# M602A.net
KiCad netlist of a schematic drawn in EAGLE
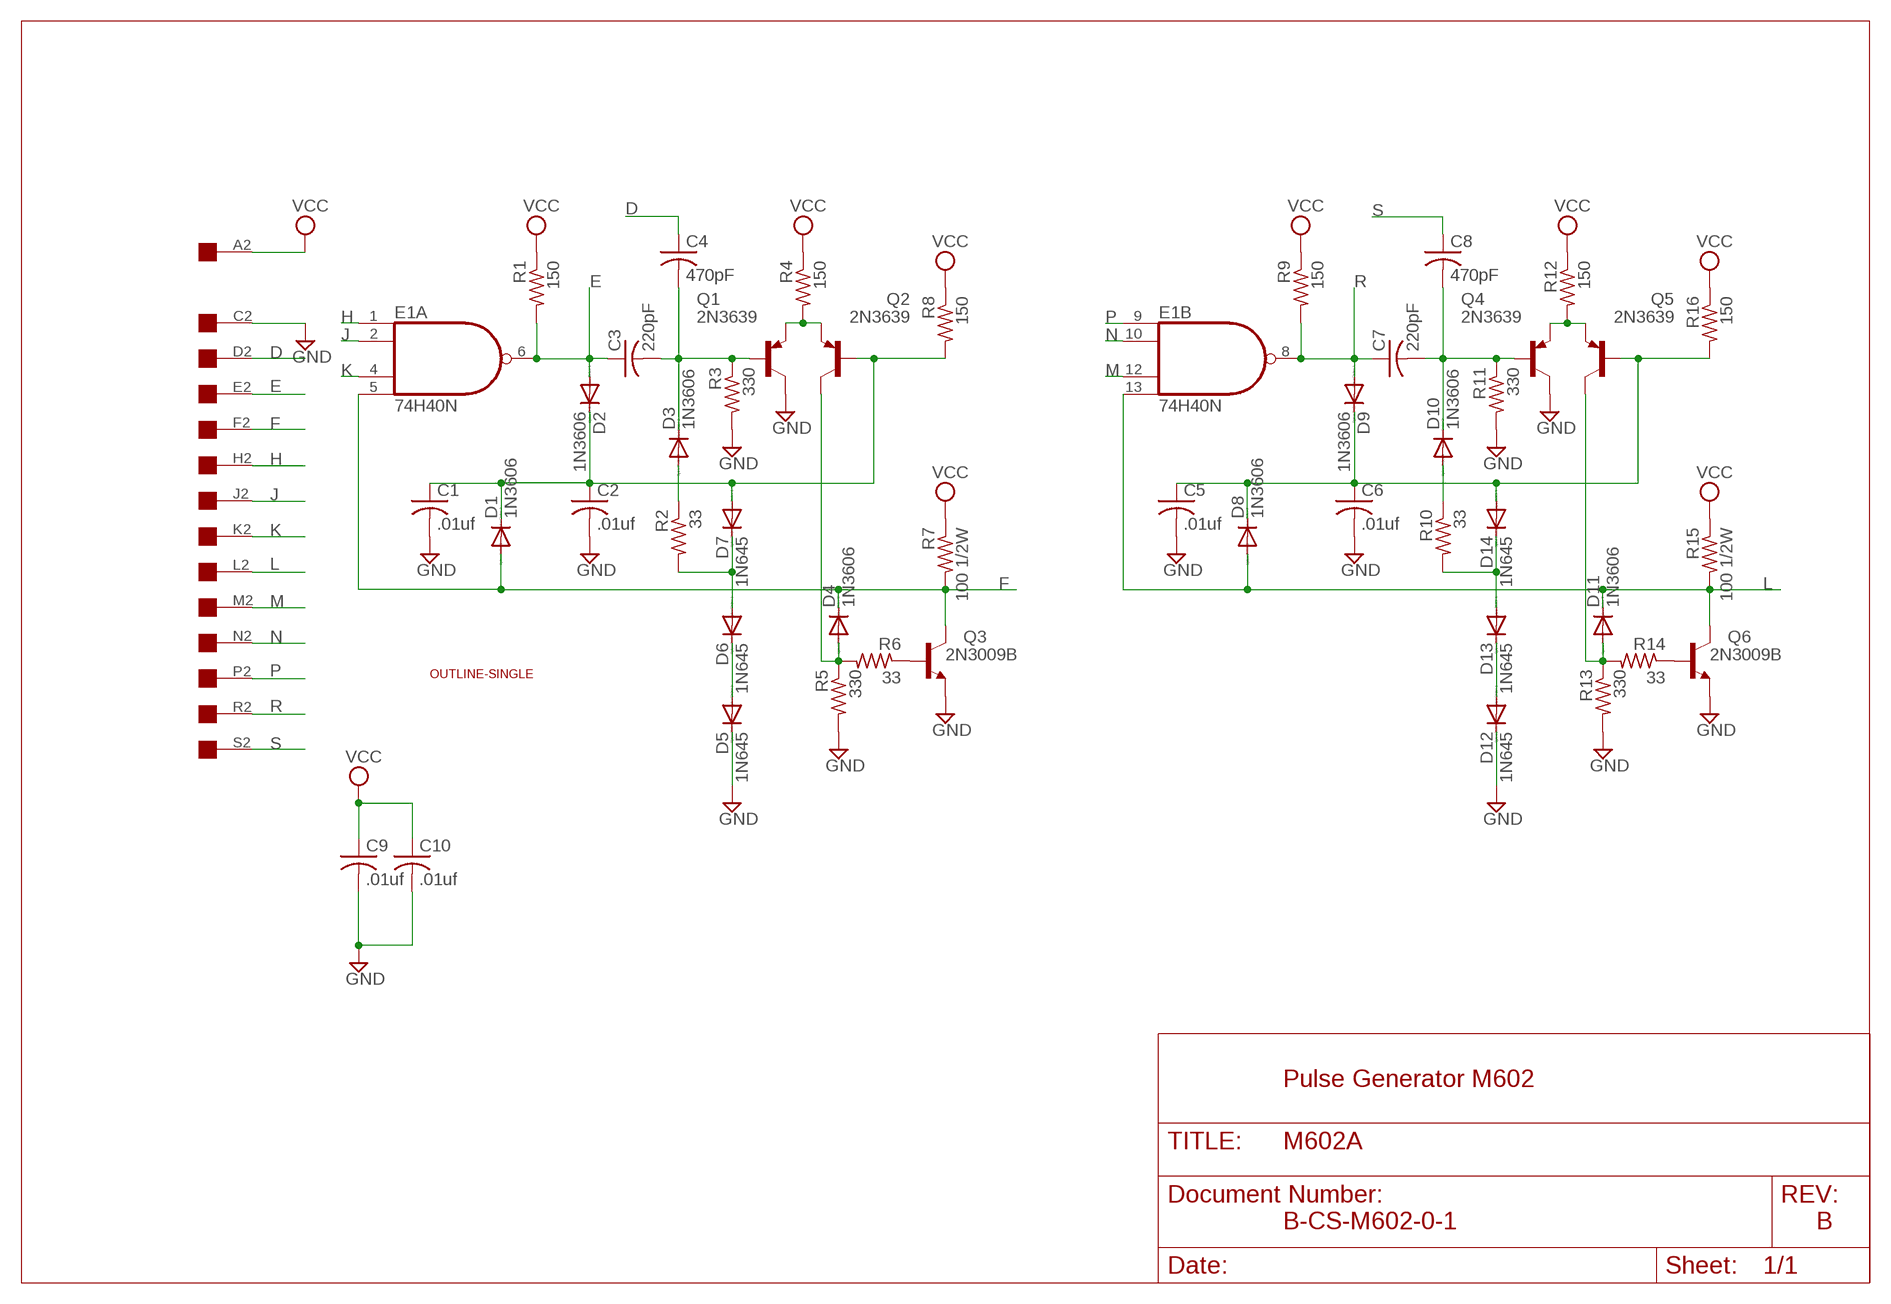
[diagram p0: schematic, sheet 1]

(export (version "E")
  (design (tool "Eeschema 10.0.6"))
  (components
    (comp (ref "C1")
      (value ".01uf")
      (footprint "eagle-import:C075-032X103")
      (libsource (lib "eagle-import") (part "C-US075-032X103"))
    )
    (comp (ref "C2")
      (value ".01uf")
      (footprint "eagle-import:C075-032X103")
      (libsource (lib "eagle-import") (part "C-US075-032X103"))
    )
    (comp (ref "C3")
      (value "220pF")
      (footprint "eagle-import:C150-054X183")
      (libsource (lib "eagle-import") (part "C-US150-054X183"))
    )
    (comp (ref "C4")
      (value "470pF")
      (footprint "eagle-import:C150-054X183")
      (libsource (lib "eagle-import") (part "C-US150-054X183"))
    )
    (comp (ref "C5")
      (value ".01uf")
      (footprint "eagle-import:C075-032X103")
      (libsource (lib "eagle-import") (part "C-US075-032X103"))
    )
    (comp (ref "C6")
      (value ".01uf")
      (footprint "eagle-import:C075-032X103")
      (libsource (lib "eagle-import") (part "C-US075-032X103"))
    )
    (comp (ref "C7")
      (value "220pF")
      (footprint "eagle-import:C150-054X183")
      (libsource (lib "eagle-import") (part "C-US150-054X183"))
    )
    (comp (ref "C8")
      (value "470pF")
      (footprint "eagle-import:C150-054X183")
      (libsource (lib "eagle-import") (part "C-US150-054X183"))
    )
    (comp (ref "C9")
      (value ".01uf")
      (footprint "eagle-import:C050-025X075")
      (libsource (lib "eagle-import") (part "C-US050-025X075"))
    )
    (comp (ref "C10")
      (value ".01uf")
      (footprint "eagle-import:C075-032X103")
      (libsource (lib "eagle-import") (part "C-US075-032X103"))
    )
    (comp (ref "D1")
      (value "1N3606")
      (footprint "eagle-import:DO41-10")
      (libsource (lib "eagle-import") (part "1N4004"))
    )
    (comp (ref "D2")
      (value "1N3606")
      (footprint "eagle-import:DO41-10")
      (libsource (lib "eagle-import") (part "1N4004"))
    )
    (comp (ref "D3")
      (value "1N3606")
      (footprint "eagle-import:DO41-10")
      (libsource (lib "eagle-import") (part "1N4004"))
    )
    (comp (ref "D4")
      (value "1N3606")
      (footprint "eagle-import:DO41-10")
      (libsource (lib "eagle-import") (part "1N4004"))
    )
    (comp (ref "D5")
      (value "1N645")
      (footprint "eagle-import:DO41-10")
      (libsource (lib "eagle-import") (part "1N4004"))
    )
    (comp (ref "D6")
      (value "1N645")
      (footprint "eagle-import:DO41-10")
      (libsource (lib "eagle-import") (part "1N4004"))
    )
    (comp (ref "D7")
      (value "1N645")
      (footprint "eagle-import:DO41-10")
      (libsource (lib "eagle-import") (part "1N4004"))
    )
    (comp (ref "D8")
      (value "1N3606")
      (footprint "eagle-import:DO41-10")
      (libsource (lib "eagle-import") (part "1N4004"))
    )
    (comp (ref "D9")
      (value "1N3606")
      (footprint "eagle-import:DO41-10")
      (libsource (lib "eagle-import") (part "1N4004"))
    )
    (comp (ref "D10")
      (value "1N3606")
      (footprint "eagle-import:DO41-10")
      (libsource (lib "eagle-import") (part "1N4004"))
    )
    (comp (ref "D11")
      (value "1N3606")
      (footprint "eagle-import:DO41-10")
      (libsource (lib "eagle-import") (part "1N4004"))
    )
    (comp (ref "D12")
      (value "1N645")
      (footprint "eagle-import:DO41-10")
      (libsource (lib "eagle-import") (part "1N4004"))
    )
    (comp (ref "D13")
      (value "1N645")
      (footprint "eagle-import:DO41-10")
      (libsource (lib "eagle-import") (part "1N4004"))
    )
    (comp (ref "D14")
      (value "1N645")
      (footprint "eagle-import:DO41-10")
      (libsource (lib "eagle-import") (part "1N4004"))
    )
    (comp (ref "E1")
      (value "74H40N")
      (footprint "eagle-import:DIL14")
      (libsource (lib "eagle-import") (part "7420NLS"))
    )
    (comp (ref "Q1")
      (value "2N3639")
      (footprint "eagle-import:TO39")
      (libsource (lib "eagle-import") (part "2N5415"))
    )
    (comp (ref "Q2")
      (value "2N3639")
      (footprint "eagle-import:TO39")
      (libsource (lib "eagle-import") (part "2N5415"))
    )
    (comp (ref "Q3")
      (value "2N3009B")
      (footprint "eagle-import:TO39")
      (libsource (lib "eagle-import") (part "2N1711"))
    )
    (comp (ref "Q4")
      (value "2N3639")
      (footprint "eagle-import:TO39")
      (libsource (lib "eagle-import") (part "2N5415"))
    )
    (comp (ref "Q5")
      (value "2N3639")
      (footprint "eagle-import:TO39")
      (libsource (lib "eagle-import") (part "2N5415"))
    )
    (comp (ref "Q6")
      (value "2N3009B")
      (footprint "eagle-import:TO39")
      (libsource (lib "eagle-import") (part "2N1711"))
    )
    (comp (ref "R1")
      (value "150")
      (footprint "eagle-import:0207_10")
      (libsource (lib "eagle-import") (part "R-US_0207/10"))
    )
    (comp (ref "R2")
      (value "33")
      (footprint "eagle-import:0207_10")
      (libsource (lib "eagle-import") (part "R-US_0207/10"))
    )
    (comp (ref "R3")
      (value "330")
      (footprint "eagle-import:0207_10")
      (libsource (lib "eagle-import") (part "R-US_0207/10"))
    )
    (comp (ref "R4")
      (value "150")
      (footprint "eagle-import:0207_10")
      (libsource (lib "eagle-import") (part "R-US_0207/10"))
    )
    (comp (ref "R5")
      (value "330")
      (footprint "eagle-import:0207_10")
      (libsource (lib "eagle-import") (part "R-US_0207/10"))
    )
    (comp (ref "R6")
      (value "33")
      (footprint "eagle-import:0207_10")
      (libsource (lib "eagle-import") (part "R-US_0207/10"))
    )
    (comp (ref "R7")
      (value "100 1/2W")
      (footprint "eagle-import:0309_12")
      (libsource (lib "eagle-import") (part "R-US_0309/12"))
    )
    (comp (ref "R8")
      (value "150")
      (footprint "eagle-import:0207_10")
      (libsource (lib "eagle-import") (part "R-US_0207/10"))
    )
    (comp (ref "R9")
      (value "150")
      (footprint "eagle-import:0207_10")
      (libsource (lib "eagle-import") (part "R-US_0207/10"))
    )
    (comp (ref "R10")
      (value "33")
      (footprint "eagle-import:0207_10")
      (libsource (lib "eagle-import") (part "R-US_0207/10"))
    )
    (comp (ref "R11")
      (value "330")
      (footprint "eagle-import:0207_10")
      (libsource (lib "eagle-import") (part "R-US_0207/10"))
    )
    (comp (ref "R12")
      (value "150")
      (footprint "eagle-import:0207_10")
      (libsource (lib "eagle-import") (part "R-US_0207/10"))
    )
    (comp (ref "R13")
      (value "330")
      (footprint "eagle-import:0207_10")
      (libsource (lib "eagle-import") (part "R-US_0207/10"))
    )
    (comp (ref "R14")
      (value "33")
      (footprint "eagle-import:0207_10")
      (libsource (lib "eagle-import") (part "R-US_0207/10"))
    )
    (comp (ref "R15")
      (value "100 1/2W")
      (footprint "eagle-import:0309_12")
      (libsource (lib "eagle-import") (part "R-US_0309/12"))
    )
    (comp (ref "R16")
      (value "150")
      (footprint "eagle-import:0207_10")
      (libsource (lib "eagle-import") (part "R-US_0207/10"))
    )
    (comp (ref "U$1")
      (value "EDGE-1")
      (footprint "eagle-import:EDGE-CON1")
      (libsource (lib "eagle-import") (part "EDGE-1"))
    )
    (comp (ref "U$2")
      (value "OUTLINE-SINGLE")
      (footprint "eagle-import:SINGLE")
      (libsource (lib "eagle-import") (part "OUTLINE-SINGLE"))
    )
  )
  (nets
    (net (code "1") (name "/D") (class "Default")
      (node (ref "C4") (pin "1") (pinfunction "1_1") (pintype "passive"))
      (node (ref "U$1") (pin "D2") (pinfunction "1_D2") (pintype "bidirectional"))
    )
    (net (code "2") (name "/E") (class "Default")
      (node (ref "C3") (pin "1") (pinfunction "1_1") (pintype "passive"))
      (node (ref "D2") (pin "A") (pinfunction "A_A") (pintype "passive"))
      (node (ref "E1") (pin "6") (pinfunction "O_6") (pintype "output"))
      (node (ref "R1") (pin "2") (pinfunction "2_2") (pintype "passive"))
      (node (ref "U$1") (pin "E2") (pinfunction "1_E2") (pintype "bidirectional"))
    )
    (net (code "3") (name "/F") (class "Default")
      (node (ref "D1") (pin "A") (pinfunction "A_A") (pintype "passive"))
      (node (ref "D4") (pin "C") (pinfunction "C_C") (pintype "passive"))
      (node (ref "E1") (pin "5") (pinfunction "I3_5") (pintype "input"))
      (node (ref "Q3") (pin "3") (pinfunction "C_3") (pintype "passive"))
      (node (ref "R7") (pin "2") (pinfunction "2_2") (pintype "passive"))
      (node (ref "U$1") (pin "F2") (pinfunction "1_F2") (pintype "bidirectional"))
    )
    (net (code "4") (name "/H") (class "Default")
      (node (ref "E1") (pin "1") (pinfunction "I0_1") (pintype "input"))
      (node (ref "U$1") (pin "H2") (pinfunction "1_H2") (pintype "bidirectional"))
    )
    (net (code "5") (name "/J") (class "Default")
      (node (ref "E1") (pin "2") (pinfunction "I1_2") (pintype "input"))
      (node (ref "U$1") (pin "J2") (pinfunction "1_J2") (pintype "bidirectional"))
    )
    (net (code "6") (name "/K") (class "Default")
      (node (ref "E1") (pin "4") (pinfunction "I2_4") (pintype "input"))
      (node (ref "U$1") (pin "K2") (pinfunction "1_K2") (pintype "bidirectional"))
    )
    (net (code "7") (name "/L") (class "Default")
      (node (ref "D11") (pin "C") (pinfunction "C_C") (pintype "passive"))
      (node (ref "D8") (pin "A") (pinfunction "A_A") (pintype "passive"))
      (node (ref "E1") (pin "13") (pinfunction "I3_13") (pintype "input"))
      (node (ref "Q6") (pin "3") (pinfunction "C_3") (pintype "passive"))
      (node (ref "R15") (pin "2") (pinfunction "2_2") (pintype "passive"))
      (node (ref "U$1") (pin "L2") (pinfunction "1_L2") (pintype "bidirectional"))
    )
    (net (code "8") (name "/M") (class "Default")
      (node (ref "E1") (pin "12") (pinfunction "I2_12") (pintype "input"))
      (node (ref "U$1") (pin "M2") (pinfunction "1_M2") (pintype "bidirectional"))
    )
    (net (code "9") (name "/N") (class "Default")
      (node (ref "E1") (pin "10") (pinfunction "I1_10") (pintype "input"))
      (node (ref "U$1") (pin "N2") (pinfunction "1_N2") (pintype "bidirectional"))
    )
    (net (code "10") (name "/P") (class "Default")
      (node (ref "E1") (pin "9") (pinfunction "I0_9") (pintype "input"))
      (node (ref "U$1") (pin "P2") (pinfunction "1_P2") (pintype "bidirectional"))
    )
    (net (code "11") (name "/R") (class "Default")
      (node (ref "C7") (pin "1") (pinfunction "1_1") (pintype "passive"))
      (node (ref "D9") (pin "A") (pinfunction "A_A") (pintype "passive"))
      (node (ref "E1") (pin "8") (pinfunction "O_8") (pintype "output"))
      (node (ref "R9") (pin "2") (pinfunction "2_2") (pintype "passive"))
      (node (ref "U$1") (pin "R2") (pinfunction "1_R2") (pintype "bidirectional"))
    )
    (net (code "12") (name "/S") (class "Default")
      (node (ref "C8") (pin "1") (pinfunction "1_1") (pintype "passive"))
      (node (ref "U$1") (pin "S2") (pinfunction "1_S2") (pintype "bidirectional"))
    )
    (net (code "13") (name "GND") (class "Default")
      (node (ref "C1") (pin "2") (pinfunction "2_2") (pintype "passive"))
      (node (ref "C10") (pin "2") (pinfunction "2_2") (pintype "passive"))
      (node (ref "C2") (pin "2") (pinfunction "2_2") (pintype "passive"))
      (node (ref "C5") (pin "2") (pinfunction "2_2") (pintype "passive"))
      (node (ref "C6") (pin "2") (pinfunction "2_2") (pintype "passive"))
      (node (ref "C9") (pin "2") (pinfunction "2_2") (pintype "passive"))
      (node (ref "D12") (pin "C") (pinfunction "C_C") (pintype "passive"))
      (node (ref "D5") (pin "C") (pinfunction "C_C") (pintype "passive"))
      (node (ref "Q1") (pin "3") (pinfunction "C_3") (pintype "passive"))
      (node (ref "Q3") (pin "1") (pinfunction "E_1") (pintype "passive"))
      (node (ref "Q4") (pin "3") (pinfunction "C_3") (pintype "passive"))
      (node (ref "Q6") (pin "1") (pinfunction "E_1") (pintype "passive"))
      (node (ref "R11") (pin "2") (pinfunction "2_2") (pintype "passive"))
      (node (ref "R13") (pin "2") (pinfunction "2_2") (pintype "passive"))
      (node (ref "R3") (pin "2") (pinfunction "2_2") (pintype "passive"))
      (node (ref "R5") (pin "2") (pinfunction "2_2") (pintype "passive"))
      (node (ref "U$1") (pin "C2") (pinfunction "1_C2") (pintype "bidirectional"))
    )
    (net (code "14") (name "Net-(D3-PadA)") (class "Default")
      (node (ref "D3") (pin "A") (pinfunction "A_A") (pintype "passive"))
      (node (ref "R2") (pin "1") (pinfunction "1_1") (pintype "passive"))
    )
    (net (code "15") (name "Net-(D5-PadA)") (class "Default")
      (node (ref "D5") (pin "A") (pinfunction "A_A") (pintype "passive"))
      (node (ref "D6") (pin "C") (pinfunction "C_C") (pintype "passive"))
    )
    (net (code "16") (name "Net-(D6-PadA)") (class "Default")
      (node (ref "D6") (pin "A") (pinfunction "A_A") (pintype "passive"))
      (node (ref "D7") (pin "C") (pinfunction "C_C") (pintype "passive"))
      (node (ref "R2") (pin "2") (pinfunction "2_2") (pintype "passive"))
    )
    (net (code "17") (name "Net-(D10-PadA)") (class "Default")
      (node (ref "D10") (pin "A") (pinfunction "A_A") (pintype "passive"))
      (node (ref "R10") (pin "1") (pinfunction "1_1") (pintype "passive"))
    )
    (net (code "18") (name "Net-(D12-PadA)") (class "Default")
      (node (ref "D12") (pin "A") (pinfunction "A_A") (pintype "passive"))
      (node (ref "D13") (pin "C") (pinfunction "C_C") (pintype "passive"))
    )
    (net (code "19") (name "Net-(D13-PadA)") (class "Default")
      (node (ref "D13") (pin "A") (pinfunction "A_A") (pintype "passive"))
      (node (ref "D14") (pin "C") (pinfunction "C_C") (pintype "passive"))
      (node (ref "R10") (pin "2") (pinfunction "2_2") (pintype "passive"))
    )
    (net (code "20") (name "Net-(Q1-B)") (class "Default")
      (node (ref "C3") (pin "2") (pinfunction "2_2") (pintype "passive"))
      (node (ref "C4") (pin "2") (pinfunction "2_2") (pintype "passive"))
      (node (ref "D3") (pin "C") (pinfunction "C_C") (pintype "passive"))
      (node (ref "Q1") (pin "2") (pinfunction "B_2") (pintype "passive"))
      (node (ref "R3") (pin "1") (pinfunction "1_1") (pintype "passive"))
    )
    (net (code "21") (name "Net-(Q1-E)") (class "Default")
      (node (ref "Q1") (pin "1") (pinfunction "E_1") (pintype "passive"))
      (node (ref "Q2") (pin "1") (pinfunction "E_1") (pintype "passive"))
      (node (ref "R4") (pin "2") (pinfunction "2_2") (pintype "passive"))
    )
    (net (code "22") (name "Net-(Q2-B)") (class "Default")
      (node (ref "C1") (pin "1") (pinfunction "1_1") (pintype "passive"))
      (node (ref "C2") (pin "1") (pinfunction "1_1") (pintype "passive"))
      (node (ref "D1") (pin "C") (pinfunction "C_C") (pintype "passive"))
      (node (ref "D2") (pin "C") (pinfunction "C_C") (pintype "passive"))
      (node (ref "D7") (pin "A") (pinfunction "A_A") (pintype "passive"))
      (node (ref "Q2") (pin "2") (pinfunction "B_2") (pintype "passive"))
      (node (ref "R8") (pin "2") (pinfunction "2_2") (pintype "passive"))
    )
    (net (code "23") (name "Net-(Q2-C)") (class "Default")
      (node (ref "D4") (pin "A") (pinfunction "A_A") (pintype "passive"))
      (node (ref "Q2") (pin "3") (pinfunction "C_3") (pintype "passive"))
      (node (ref "R5") (pin "1") (pinfunction "1_1") (pintype "passive"))
      (node (ref "R6") (pin "2") (pinfunction "2_2") (pintype "passive"))
    )
    (net (code "24") (name "Net-(Q3-B)") (class "Default")
      (node (ref "Q3") (pin "2") (pinfunction "B_2") (pintype "passive"))
      (node (ref "R6") (pin "1") (pinfunction "1_1") (pintype "passive"))
    )
    (net (code "25") (name "Net-(Q4-B)") (class "Default")
      (node (ref "C7") (pin "2") (pinfunction "2_2") (pintype "passive"))
      (node (ref "C8") (pin "2") (pinfunction "2_2") (pintype "passive"))
      (node (ref "D10") (pin "C") (pinfunction "C_C") (pintype "passive"))
      (node (ref "Q4") (pin "2") (pinfunction "B_2") (pintype "passive"))
      (node (ref "R11") (pin "1") (pinfunction "1_1") (pintype "passive"))
    )
    (net (code "26") (name "Net-(Q4-E)") (class "Default")
      (node (ref "Q4") (pin "1") (pinfunction "E_1") (pintype "passive"))
      (node (ref "Q5") (pin "1") (pinfunction "E_1") (pintype "passive"))
      (node (ref "R12") (pin "2") (pinfunction "2_2") (pintype "passive"))
    )
    (net (code "27") (name "Net-(Q5-B)") (class "Default")
      (node (ref "C5") (pin "1") (pinfunction "1_1") (pintype "passive"))
      (node (ref "C6") (pin "1") (pinfunction "1_1") (pintype "passive"))
      (node (ref "D14") (pin "A") (pinfunction "A_A") (pintype "passive"))
      (node (ref "D8") (pin "C") (pinfunction "C_C") (pintype "passive"))
      (node (ref "D9") (pin "C") (pinfunction "C_C") (pintype "passive"))
      (node (ref "Q5") (pin "2") (pinfunction "B_2") (pintype "passive"))
      (node (ref "R16") (pin "2") (pinfunction "2_2") (pintype "passive"))
    )
    (net (code "28") (name "Net-(Q5-C)") (class "Default")
      (node (ref "D11") (pin "A") (pinfunction "A_A") (pintype "passive"))
      (node (ref "Q5") (pin "3") (pinfunction "C_3") (pintype "passive"))
      (node (ref "R13") (pin "1") (pinfunction "1_1") (pintype "passive"))
      (node (ref "R14") (pin "2") (pinfunction "2_2") (pintype "passive"))
    )
    (net (code "29") (name "Net-(Q6-B)") (class "Default")
      (node (ref "Q6") (pin "2") (pinfunction "B_2") (pintype "passive"))
      (node (ref "R14") (pin "1") (pinfunction "1_1") (pintype "passive"))
    )
    (net (code "30") (name "VCC") (class "Default")
      (node (ref "C10") (pin "1") (pinfunction "1_1") (pintype "passive"))
      (node (ref "C9") (pin "1") (pinfunction "1_1") (pintype "passive"))
      (node (ref "R1") (pin "1") (pinfunction "1_1") (pintype "passive"))
      (node (ref "R12") (pin "1") (pinfunction "1_1") (pintype "passive"))
      (node (ref "R15") (pin "1") (pinfunction "1_1") (pintype "passive"))
      (node (ref "R16") (pin "1") (pinfunction "1_1") (pintype "passive"))
      (node (ref "R4") (pin "1") (pinfunction "1_1") (pintype "passive"))
      (node (ref "R7") (pin "1") (pinfunction "1_1") (pintype "passive"))
      (node (ref "R8") (pin "1") (pinfunction "1_1") (pintype "passive"))
      (node (ref "R9") (pin "1") (pinfunction "1_1") (pintype "passive"))
      (node (ref "U$1") (pin "A2") (pinfunction "1_A2") (pintype "bidirectional"))
    )
  )
)
